# Controller.net
KiCad netlist of a schematic drawn in EAGLE
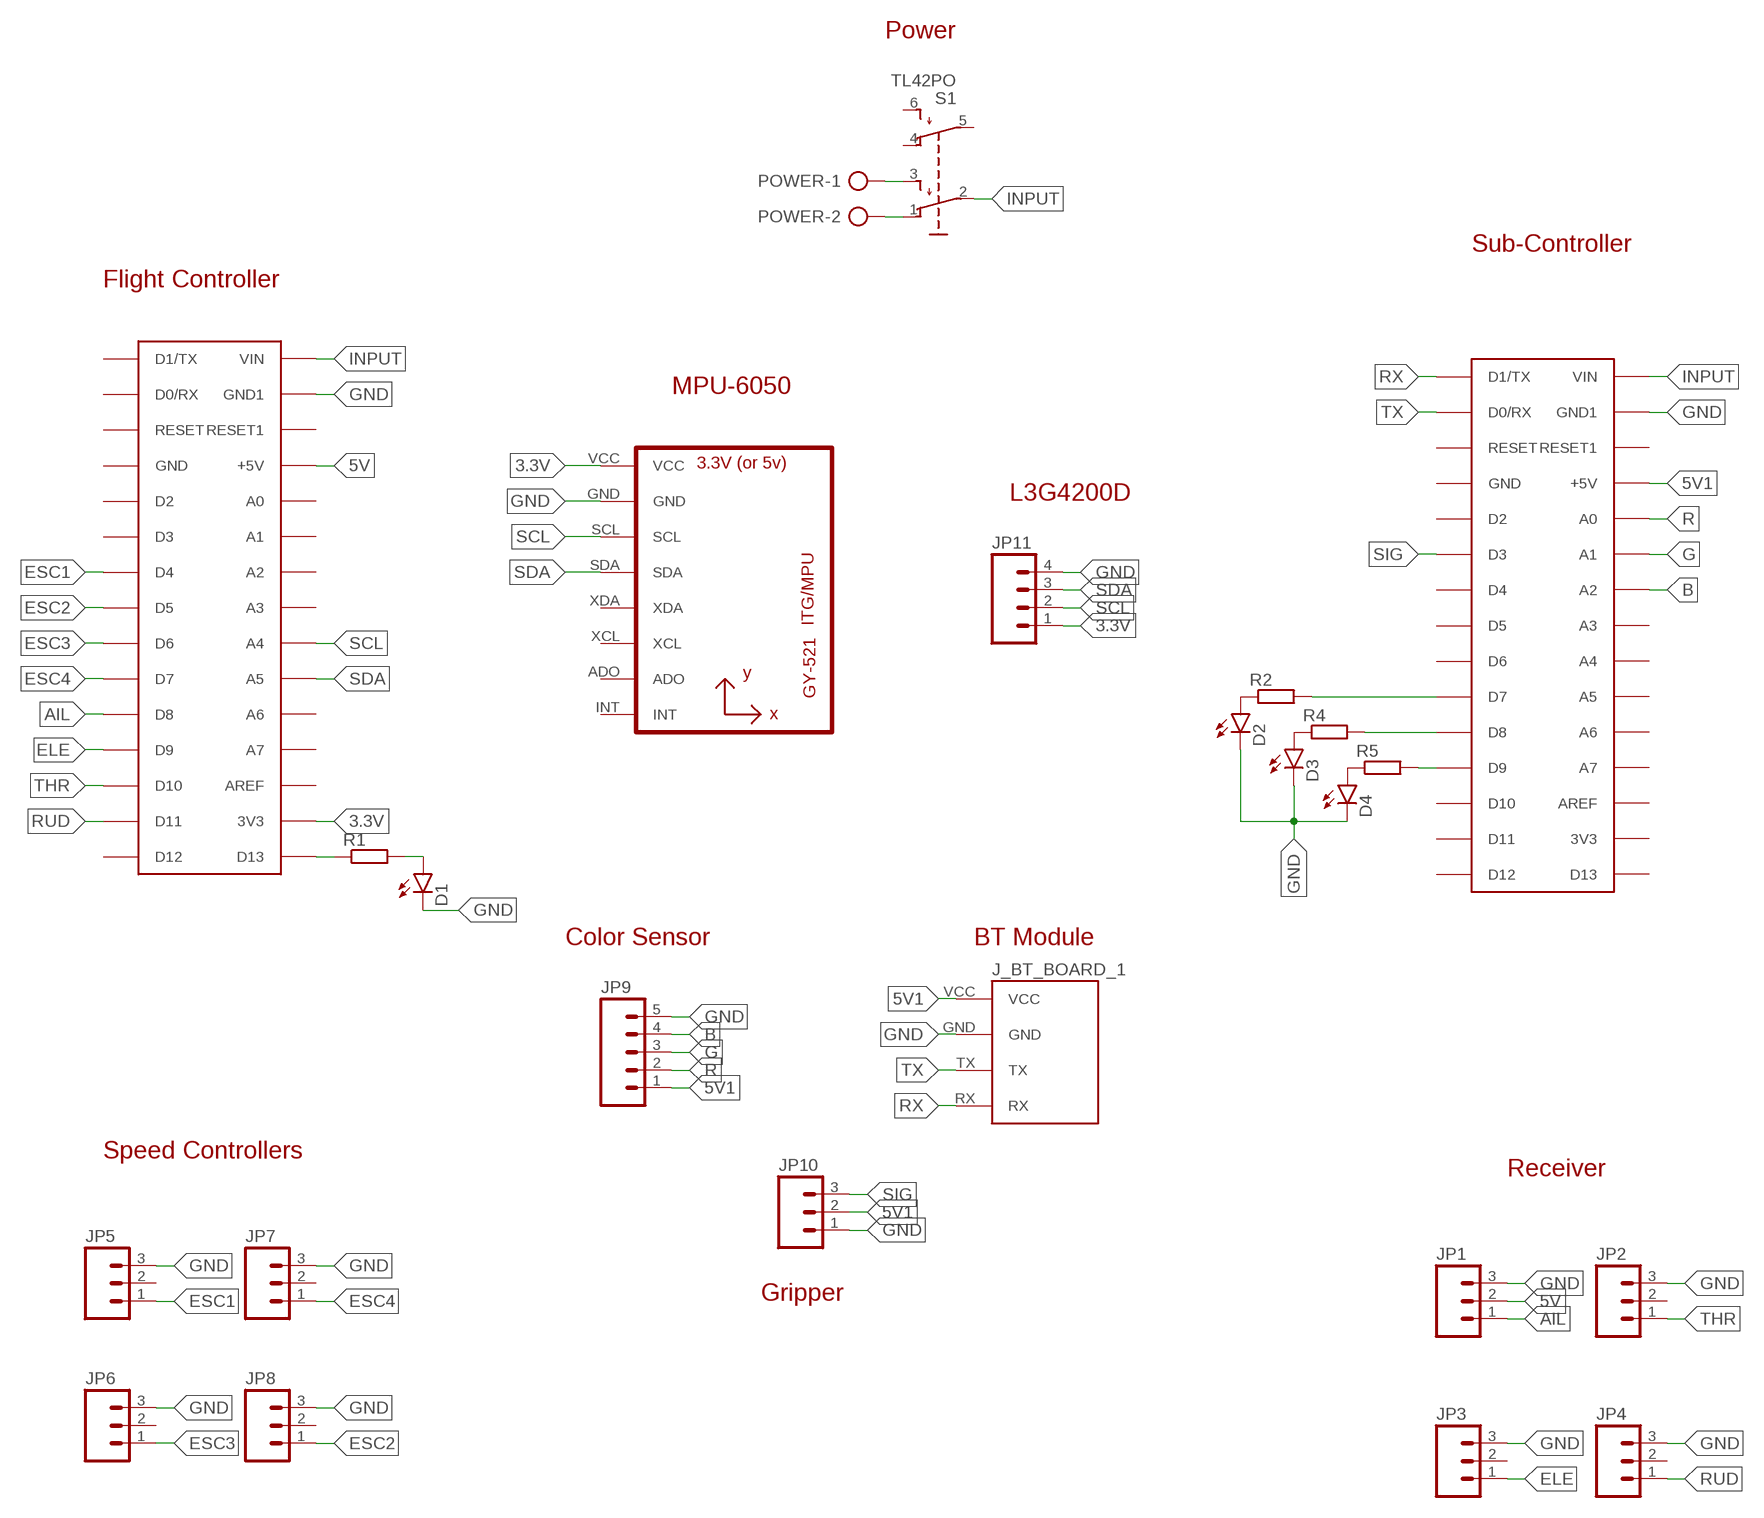
[diagram p0: schematic, sheet 1]

(export (version "E")
  (design (tool "Eeschema 10.0.6"))
  (components
    (comp (ref "D1")
      (value "LED5MM")
      (footprint "eagle-import:LED5MM")
      (libsource (lib "eagle-import") (part "LED5MM"))
    )
    (comp (ref "D2")
      (value "LED5MM")
      (footprint "eagle-import:LED5MM")
      (libsource (lib "eagle-import") (part "LED5MM"))
    )
    (comp (ref "D3")
      (value "LED5MM")
      (footprint "eagle-import:LED5MM")
      (libsource (lib "eagle-import") (part "LED5MM"))
    )
    (comp (ref "D4")
      (value "LED5MM")
      (footprint "eagle-import:LED5MM")
      (libsource (lib "eagle-import") (part "LED5MM"))
    )
    (comp (ref "JP1")
      (value "M031X03_NO_SILK")
      (footprint "eagle-import:1X03_NO_SILK")
      (libsource (lib "eagle-import") (part "M031X03_NO_SILK"))
    )
    (comp (ref "JP2")
      (value "M031X03_NO_SILK")
      (footprint "eagle-import:1X03_NO_SILK")
      (libsource (lib "eagle-import") (part "M031X03_NO_SILK"))
    )
    (comp (ref "JP3")
      (value "M031X03_NO_SILK")
      (footprint "eagle-import:1X03_NO_SILK")
      (libsource (lib "eagle-import") (part "M031X03_NO_SILK"))
    )
    (comp (ref "JP4")
      (value "M031X03_NO_SILK")
      (footprint "eagle-import:1X03_NO_SILK")
      (libsource (lib "eagle-import") (part "M031X03_NO_SILK"))
    )
    (comp (ref "JP5")
      (value "M031X03_NO_SILK")
      (footprint "eagle-import:1X03_NO_SILK")
      (libsource (lib "eagle-import") (part "M031X03_NO_SILK"))
    )
    (comp (ref "JP6")
      (value "M031X03_NO_SILK")
      (footprint "eagle-import:1X03_NO_SILK")
      (libsource (lib "eagle-import") (part "M031X03_NO_SILK"))
    )
    (comp (ref "JP7")
      (value "M031X03_NO_SILK")
      (footprint "eagle-import:1X03_NO_SILK")
      (libsource (lib "eagle-import") (part "M031X03_NO_SILK"))
    )
    (comp (ref "JP8")
      (value "M031X03_NO_SILK")
      (footprint "eagle-import:1X03_NO_SILK")
      (libsource (lib "eagle-import") (part "M031X03_NO_SILK"))
    )
    (comp (ref "JP9")
      (value "M05NO_SILK")
      (footprint "eagle-import:1X05_NO_SILK")
      (libsource (lib "eagle-import") (part "M05NO_SILK"))
    )
    (comp (ref "JP10")
      (value "M031X03_NO_SILK")
      (footprint "eagle-import:1X03_NO_SILK")
      (libsource (lib "eagle-import") (part "M031X03_NO_SILK"))
    )
    (comp (ref "JP11")
      (value "M04NO_SILK_ALL_ROUND")
      (footprint "eagle-import:1X04_NO_SILK_ALL_ROUND")
      (libsource (lib "eagle-import") (part "M04NO_SILK_ALL_ROUND"))
    )
    (comp (ref "J_BT_BOARD_1")
      (value "BLUETOOTH_BOARDSTANDING")
      (footprint "eagle-import:BT_BOARD_FOOTPRINT_STANDING")
      (libsource (lib "eagle-import") (part "BLUETOOTH_BOARDSTANDING"))
    )
    (comp (ref "POWER")
      (value "AK300/2")
      (footprint "eagle-import:AK300_2")
      (libsource (lib "eagle-import") (part "AK300/2"))
    )
    (comp (ref "R1")
      (value "R-EU_0207/10")
      (footprint "eagle-import:0207_10")
      (libsource (lib "eagle-import") (part "R-EU_0207/10"))
    )
    (comp (ref "R2")
      (value "R-EU_0207/10")
      (footprint "eagle-import:0207_10")
      (libsource (lib "eagle-import") (part "R-EU_0207/10"))
    )
    (comp (ref "R4")
      (value "R-EU_0207/10")
      (footprint "eagle-import:0207_10")
      (libsource (lib "eagle-import") (part "R-EU_0207/10"))
    )
    (comp (ref "R5")
      (value "R-EU_0207/10")
      (footprint "eagle-import:0207_10")
      (libsource (lib "eagle-import") (part "R-EU_0207/10"))
    )
    (comp (ref "S1")
      (value "TL42PO")
      (footprint "eagle-import:TL4XPO")
      (libsource (lib "eagle-import") (part "TL42PO"))
    )
    (comp (ref "U$1")
      (value "ARDUINONANO")
      (footprint "eagle-import:PDIP-32")
      (libsource (lib "eagle-import") (part "ARDUINONANO"))
    )
    (comp (ref "U$2")
      (value "ARDUINONANO")
      (footprint "eagle-import:PDIP-32")
      (libsource (lib "eagle-import") (part "ARDUINONANO"))
    )
    (comp (ref "U1")
      (value "GY-521MPU6050")
      (footprint "eagle-import:GY-521")
      (libsource (lib "eagle-import") (part "GY-521MPU6050"))
    )
  )
  (nets
    (net (code "1") (name "3.3V") (class "Default")
      (node (ref "JP11") (pin "1") (pinfunction "1_1") (pintype "passive"))
      (node (ref "U$1") (pin "3V3") (pinfunction "3V3_3V3") (pintype "bidirectional"))
      (node (ref "U1") (pin "VCC") (pinfunction "VCC_VCC") (pintype "bidirectional"))
    )
    (net (code "2") (name "5V") (class "Default")
      (node (ref "JP1") (pin "2") (pinfunction "2_2") (pintype "passive"))
      (node (ref "U$1") (pin "+5V") (pinfunction "+5V_+5V") (pintype "bidirectional"))
    )
    (net (code "3") (name "5V1") (class "Default")
      (node (ref "JP10") (pin "2") (pinfunction "2_2") (pintype "passive"))
      (node (ref "JP9") (pin "1") (pinfunction "1_1") (pintype "passive"))
      (node (ref "J_BT_BOARD_1") (pin "VCC") (pinfunction "VCC_VCC") (pintype "bidirectional"))
      (node (ref "U$2") (pin "+5V") (pinfunction "+5V_+5V") (pintype "bidirectional"))
    )
    (net (code "4") (name "AIL") (class "Default")
      (node (ref "JP1") (pin "1") (pinfunction "1_1") (pintype "passive"))
      (node (ref "U$1") (pin "D8") (pinfunction "D8_D8") (pintype "bidirectional"))
    )
    (net (code "5") (name "B") (class "Default")
      (node (ref "JP9") (pin "4") (pinfunction "4_4") (pintype "passive"))
      (node (ref "U$2") (pin "A2") (pinfunction "A2_A2") (pintype "bidirectional"))
    )
    (net (code "6") (name "ELE") (class "Default")
      (node (ref "JP3") (pin "1") (pinfunction "1_1") (pintype "passive"))
      (node (ref "U$1") (pin "D9") (pinfunction "D9_D9") (pintype "bidirectional"))
    )
    (net (code "7") (name "ESC1") (class "Default")
      (node (ref "JP5") (pin "1") (pinfunction "1_1") (pintype "passive"))
      (node (ref "U$1") (pin "D4") (pinfunction "D4_D4") (pintype "bidirectional"))
    )
    (net (code "8") (name "ESC2") (class "Default")
      (node (ref "JP8") (pin "1") (pinfunction "1_1") (pintype "passive"))
      (node (ref "U$1") (pin "D5") (pinfunction "D5_D5") (pintype "bidirectional"))
    )
    (net (code "9") (name "ESC3") (class "Default")
      (node (ref "JP6") (pin "1") (pinfunction "1_1") (pintype "passive"))
      (node (ref "U$1") (pin "D6") (pinfunction "D6_D6") (pintype "bidirectional"))
    )
    (net (code "10") (name "ESC4") (class "Default")
      (node (ref "JP7") (pin "1") (pinfunction "1_1") (pintype "passive"))
      (node (ref "U$1") (pin "D7") (pinfunction "D7_D7") (pintype "bidirectional"))
    )
    (net (code "11") (name "G") (class "Default")
      (node (ref "JP9") (pin "3") (pinfunction "3_3") (pintype "passive"))
      (node (ref "U$2") (pin "A1") (pinfunction "A1_A1") (pintype "bidirectional"))
    )
    (net (code "12") (name "GND") (class "Default")
      (node (ref "D1") (pin "K") (pinfunction "C_K") (pintype "passive"))
      (node (ref "D2") (pin "K") (pinfunction "C_K") (pintype "passive"))
      (node (ref "D3") (pin "K") (pinfunction "C_K") (pintype "passive"))
      (node (ref "D4") (pin "K") (pinfunction "C_K") (pintype "passive"))
      (node (ref "JP1") (pin "3") (pinfunction "3_3") (pintype "passive"))
      (node (ref "JP10") (pin "1") (pinfunction "1_1") (pintype "passive"))
      (node (ref "JP11") (pin "4") (pinfunction "4_4") (pintype "passive"))
      (node (ref "JP2") (pin "3") (pinfunction "3_3") (pintype "passive"))
      (node (ref "JP3") (pin "3") (pinfunction "3_3") (pintype "passive"))
      (node (ref "JP4") (pin "3") (pinfunction "3_3") (pintype "passive"))
      (node (ref "JP5") (pin "3") (pinfunction "3_3") (pintype "passive"))
      (node (ref "JP6") (pin "3") (pinfunction "3_3") (pintype "passive"))
      (node (ref "JP7") (pin "3") (pinfunction "3_3") (pintype "passive"))
      (node (ref "JP8") (pin "3") (pinfunction "3_3") (pintype "passive"))
      (node (ref "JP9") (pin "5") (pinfunction "5_5") (pintype "passive"))
      (node (ref "J_BT_BOARD_1") (pin "GND") (pinfunction "GND_GND") (pintype "bidirectional"))
      (node (ref "POWER") (pin "1") (pinfunction "KL_1") (pintype "passive"))
      (node (ref "S1") (pin "3") (pinfunction "S_3") (pintype "passive"))
      (node (ref "U$1") (pin "GND1") (pinfunction "GND1_GND1") (pintype "bidirectional"))
      (node (ref "U$2") (pin "GND1") (pinfunction "GND1_GND1") (pintype "bidirectional"))
      (node (ref "U1") (pin "GND") (pinfunction "GND_GND") (pintype "bidirectional"))
    )
    (net (code "13") (name "INPUT") (class "Default")
      (node (ref "S1") (pin "2") (pinfunction "P_2") (pintype "passive"))
      (node (ref "U$1") (pin "VIN") (pinfunction "VIN_VIN") (pintype "bidirectional"))
      (node (ref "U$2") (pin "VIN") (pinfunction "VIN_VIN") (pintype "bidirectional"))
    )
    (net (code "14") (name "Net-(D1-PadA)") (class "Default")
      (node (ref "D1") (pin "A") (pinfunction "A_A") (pintype "passive"))
      (node (ref "R1") (pin "2") (pinfunction "2_2") (pintype "passive"))
    )
    (net (code "15") (name "Net-(D2-PadA)") (class "Default")
      (node (ref "D2") (pin "A") (pinfunction "A_A") (pintype "passive"))
      (node (ref "R2") (pin "1") (pinfunction "1_1") (pintype "passive"))
    )
    (net (code "16") (name "Net-(D3-PadA)") (class "Default")
      (node (ref "D3") (pin "A") (pinfunction "A_A") (pintype "passive"))
      (node (ref "R4") (pin "1") (pinfunction "1_1") (pintype "passive"))
    )
    (net (code "17") (name "Net-(D4-PadA)") (class "Default")
      (node (ref "D4") (pin "A") (pinfunction "A_A") (pintype "passive"))
      (node (ref "R5") (pin "1") (pinfunction "1_1") (pintype "passive"))
    )
    (net (code "18") (name "Net-(POWERB-KL)") (class "Default")
      (node (ref "POWER") (pin "2") (pinfunction "KL_2") (pintype "passive"))
      (node (ref "S1") (pin "1") (pinfunction "O_1") (pintype "passive"))
    )
    (net (code "19") (name "Net-(R1-Pad1)") (class "Default")
      (node (ref "R1") (pin "1") (pinfunction "1_1") (pintype "passive"))
      (node (ref "U$1") (pin "D13") (pinfunction "D13_D13") (pintype "bidirectional"))
    )
    (net (code "20") (name "Net-(R2-Pad2)") (class "Default")
      (node (ref "R2") (pin "2") (pinfunction "2_2") (pintype "passive"))
      (node (ref "U$2") (pin "D7") (pinfunction "D7_D7") (pintype "bidirectional"))
    )
    (net (code "21") (name "Net-(R4-Pad2)") (class "Default")
      (node (ref "R4") (pin "2") (pinfunction "2_2") (pintype "passive"))
      (node (ref "U$2") (pin "D8") (pinfunction "D8_D8") (pintype "bidirectional"))
    )
    (net (code "22") (name "Net-(R5-Pad2)") (class "Default")
      (node (ref "R5") (pin "2") (pinfunction "2_2") (pintype "passive"))
      (node (ref "U$2") (pin "D9") (pinfunction "D9_D9") (pintype "bidirectional"))
    )
    (net (code "23") (name "R") (class "Default")
      (node (ref "JP9") (pin "2") (pinfunction "2_2") (pintype "passive"))
      (node (ref "U$2") (pin "A0") (pinfunction "A0_A0") (pintype "bidirectional"))
    )
    (net (code "24") (name "RUD") (class "Default")
      (node (ref "JP4") (pin "1") (pinfunction "1_1") (pintype "passive"))
      (node (ref "U$1") (pin "D11") (pinfunction "D11_D11") (pintype "bidirectional"))
    )
    (net (code "25") (name "RX") (class "Default")
      (node (ref "J_BT_BOARD_1") (pin "RX") (pinfunction "RX_RX") (pintype "bidirectional"))
      (node (ref "U$2") (pin "D1/TX") (pinfunction "D1/TX_D1/TX") (pintype "bidirectional"))
    )
    (net (code "26") (name "SCL") (class "Default")
      (node (ref "JP11") (pin "2") (pinfunction "2_2") (pintype "passive"))
      (node (ref "U$1") (pin "A4") (pinfunction "A4_A4") (pintype "bidirectional"))
      (node (ref "U1") (pin "SCL") (pinfunction "SCL_SCL") (pintype "bidirectional"))
    )
    (net (code "27") (name "SDA") (class "Default")
      (node (ref "JP11") (pin "3") (pinfunction "3_3") (pintype "passive"))
      (node (ref "U$1") (pin "A5") (pinfunction "A5_A5") (pintype "bidirectional"))
      (node (ref "U1") (pin "SDA") (pinfunction "SDA_SDA") (pintype "bidirectional"))
    )
    (net (code "28") (name "SIG") (class "Default")
      (node (ref "JP10") (pin "3") (pinfunction "3_3") (pintype "passive"))
      (node (ref "U$2") (pin "D3") (pinfunction "D3_D3") (pintype "bidirectional"))
    )
    (net (code "29") (name "THR") (class "Default")
      (node (ref "JP2") (pin "1") (pinfunction "1_1") (pintype "passive"))
      (node (ref "U$1") (pin "D10") (pinfunction "D10_D10") (pintype "bidirectional"))
    )
    (net (code "30") (name "TX") (class "Default")
      (node (ref "J_BT_BOARD_1") (pin "TX") (pinfunction "TX_TX") (pintype "bidirectional"))
      (node (ref "U$2") (pin "D0/RX") (pinfunction "D0/RX_D0/RX") (pintype "bidirectional"))
    )
    (net (code "31") (name "unconnected-(JP2-Pad2)") (class "Default")
      (node (ref "JP2") (pin "2") (pinfunction "2_2") (pintype "passive"))
    )
    (net (code "32") (name "unconnected-(JP3-Pad2)") (class "Default")
      (node (ref "JP3") (pin "2") (pinfunction "2_2") (pintype "passive"))
    )
    (net (code "33") (name "unconnected-(JP4-Pad2)") (class "Default")
      (node (ref "JP4") (pin "2") (pinfunction "2_2") (pintype "passive"))
    )
    (net (code "34") (name "unconnected-(JP5-Pad2)") (class "Default")
      (node (ref "JP5") (pin "2") (pinfunction "2_2") (pintype "passive"))
    )
    (net (code "35") (name "unconnected-(JP6-Pad2)") (class "Default")
      (node (ref "JP6") (pin "2") (pinfunction "2_2") (pintype "passive"))
    )
    (net (code "36") (name "unconnected-(JP7-Pad2)") (class "Default")
      (node (ref "JP7") (pin "2") (pinfunction "2_2") (pintype "passive"))
    )
    (net (code "37") (name "unconnected-(JP8-Pad2)") (class "Default")
      (node (ref "JP8") (pin "2") (pinfunction "2_2") (pintype "passive"))
    )
    (net (code "38") (name "unconnected-(S1-O1-Pad4)") (class "Default")
      (node (ref "S1") (pin "4") (pinfunction "O1_4") (pintype "passive"))
    )
    (net (code "39") (name "unconnected-(S1-P1-Pad5)") (class "Default")
      (node (ref "S1") (pin "5") (pinfunction "P1_5") (pintype "passive"))
    )
    (net (code "40") (name "unconnected-(S1-S1-Pad6)") (class "Default")
      (node (ref "S1") (pin "6") (pinfunction "S1_6") (pintype "passive"))
    )
    (net (code "41") (name "unconnected-(U$1-PadA0)") (class "Default")
      (node (ref "U$1") (pin "A0") (pinfunction "A0_A0") (pintype "bidirectional"))
    )
    (net (code "42") (name "unconnected-(U$1-PadA1)") (class "Default")
      (node (ref "U$1") (pin "A1") (pinfunction "A1_A1") (pintype "bidirectional"))
    )
    (net (code "43") (name "unconnected-(U$1-PadA2)") (class "Default")
      (node (ref "U$1") (pin "A2") (pinfunction "A2_A2") (pintype "bidirectional"))
    )
    (net (code "44") (name "unconnected-(U$1-PadA3)") (class "Default")
      (node (ref "U$1") (pin "A3") (pinfunction "A3_A3") (pintype "bidirectional"))
    )
    (net (code "45") (name "unconnected-(U$1-PadA6)") (class "Default")
      (node (ref "U$1") (pin "A6") (pinfunction "A6_A6") (pintype "bidirectional"))
    )
    (net (code "46") (name "unconnected-(U$1-PadA7)") (class "Default")
      (node (ref "U$1") (pin "A7") (pinfunction "A7_A7") (pintype "bidirectional"))
    )
    (net (code "47") (name "unconnected-(U$1-PadAREF)") (class "Default")
      (node (ref "U$1") (pin "AREF") (pinfunction "AREF_AREF") (pintype "bidirectional"))
    )
    (net (code "48") (name "unconnected-(U$1-PadD0{slash}RX)") (class "Default")
      (node (ref "U$1") (pin "D0/RX") (pinfunction "D0/RX_D0/RX") (pintype "bidirectional"))
    )
    (net (code "49") (name "unconnected-(U$1-PadD1{slash}TX)") (class "Default")
      (node (ref "U$1") (pin "D1/TX") (pinfunction "D1/TX_D1/TX") (pintype "bidirectional"))
    )
    (net (code "50") (name "unconnected-(U$1-PadD2)") (class "Default")
      (node (ref "U$1") (pin "D2") (pinfunction "D2_D2") (pintype "bidirectional"))
    )
    (net (code "51") (name "unconnected-(U$1-PadD3)") (class "Default")
      (node (ref "U$1") (pin "D3") (pinfunction "D3_D3") (pintype "bidirectional"))
    )
    (net (code "52") (name "unconnected-(U$1-PadD12)") (class "Default")
      (node (ref "U$1") (pin "D12") (pinfunction "D12_D12") (pintype "bidirectional"))
    )
    (net (code "53") (name "unconnected-(U$1-PadGND)") (class "Default")
      (node (ref "U$1") (pin "GND") (pinfunction "GND_GND") (pintype "bidirectional"))
    )
    (net (code "54") (name "unconnected-(U$1-PadRESET)") (class "Default")
      (node (ref "U$1") (pin "RESET") (pinfunction "RESET_RESET") (pintype "bidirectional"))
    )
    (net (code "55") (name "unconnected-(U$1-PadRESET1)") (class "Default")
      (node (ref "U$1") (pin "RESET1") (pinfunction "RESET1_RESET1") (pintype "bidirectional"))
    )
    (net (code "56") (name "unconnected-(U$2-Pad3V3)") (class "Default")
      (node (ref "U$2") (pin "3V3") (pinfunction "3V3_3V3") (pintype "bidirectional"))
    )
    (net (code "57") (name "unconnected-(U$2-PadA3)") (class "Default")
      (node (ref "U$2") (pin "A3") (pinfunction "A3_A3") (pintype "bidirectional"))
    )
    (net (code "58") (name "unconnected-(U$2-PadA4)") (class "Default")
      (node (ref "U$2") (pin "A4") (pinfunction "A4_A4") (pintype "bidirectional"))
    )
    (net (code "59") (name "unconnected-(U$2-PadA5)") (class "Default")
      (node (ref "U$2") (pin "A5") (pinfunction "A5_A5") (pintype "bidirectional"))
    )
    (net (code "60") (name "unconnected-(U$2-PadA6)") (class "Default")
      (node (ref "U$2") (pin "A6") (pinfunction "A6_A6") (pintype "bidirectional"))
    )
    (net (code "61") (name "unconnected-(U$2-PadA7)") (class "Default")
      (node (ref "U$2") (pin "A7") (pinfunction "A7_A7") (pintype "bidirectional"))
    )
    (net (code "62") (name "unconnected-(U$2-PadAREF)") (class "Default")
      (node (ref "U$2") (pin "AREF") (pinfunction "AREF_AREF") (pintype "bidirectional"))
    )
    (net (code "63") (name "unconnected-(U$2-PadD2)") (class "Default")
      (node (ref "U$2") (pin "D2") (pinfunction "D2_D2") (pintype "bidirectional"))
    )
    (net (code "64") (name "unconnected-(U$2-PadD4)") (class "Default")
      (node (ref "U$2") (pin "D4") (pinfunction "D4_D4") (pintype "bidirectional"))
    )
    (net (code "65") (name "unconnected-(U$2-PadD5)") (class "Default")
      (node (ref "U$2") (pin "D5") (pinfunction "D5_D5") (pintype "bidirectional"))
    )
    (net (code "66") (name "unconnected-(U$2-PadD6)") (class "Default")
      (node (ref "U$2") (pin "D6") (pinfunction "D6_D6") (pintype "bidirectional"))
    )
    (net (code "67") (name "unconnected-(U$2-PadD10)") (class "Default")
      (node (ref "U$2") (pin "D10") (pinfunction "D10_D10") (pintype "bidirectional"))
    )
    (net (code "68") (name "unconnected-(U$2-PadD11)") (class "Default")
      (node (ref "U$2") (pin "D11") (pinfunction "D11_D11") (pintype "bidirectional"))
    )
    (net (code "69") (name "unconnected-(U$2-PadD12)") (class "Default")
      (node (ref "U$2") (pin "D12") (pinfunction "D12_D12") (pintype "bidirectional"))
    )
    (net (code "70") (name "unconnected-(U$2-PadD13)") (class "Default")
      (node (ref "U$2") (pin "D13") (pinfunction "D13_D13") (pintype "bidirectional"))
    )
    (net (code "71") (name "unconnected-(U$2-PadGND)") (class "Default")
      (node (ref "U$2") (pin "GND") (pinfunction "GND_GND") (pintype "bidirectional"))
    )
    (net (code "72") (name "unconnected-(U$2-PadRESET)") (class "Default")
      (node (ref "U$2") (pin "RESET") (pinfunction "RESET_RESET") (pintype "bidirectional"))
    )
    (net (code "73") (name "unconnected-(U$2-PadRESET1)") (class "Default")
      (node (ref "U$2") (pin "RESET1") (pinfunction "RESET1_RESET1") (pintype "bidirectional"))
    )
    (net (code "74") (name "unconnected-(U1-PadADO)") (class "Default")
      (node (ref "U1") (pin "ADO") (pinfunction "ADO_ADO") (pintype "bidirectional"))
    )
    (net (code "75") (name "unconnected-(U1-PadINT)") (class "Default")
      (node (ref "U1") (pin "INT") (pinfunction "INT_INT") (pintype "bidirectional"))
    )
    (net (code "76") (name "unconnected-(U1-PadXCL)") (class "Default")
      (node (ref "U1") (pin "XCL") (pinfunction "XCL_XCL") (pintype "bidirectional"))
    )
    (net (code "77") (name "unconnected-(U1-PadXDA)") (class "Default")
      (node (ref "U1") (pin "XDA") (pinfunction "XDA_XDA") (pintype "bidirectional"))
    )
  )
)
